# ISOBUS_Hardware_S3.net
KiCad netlist of a schematic drawn in EAGLE
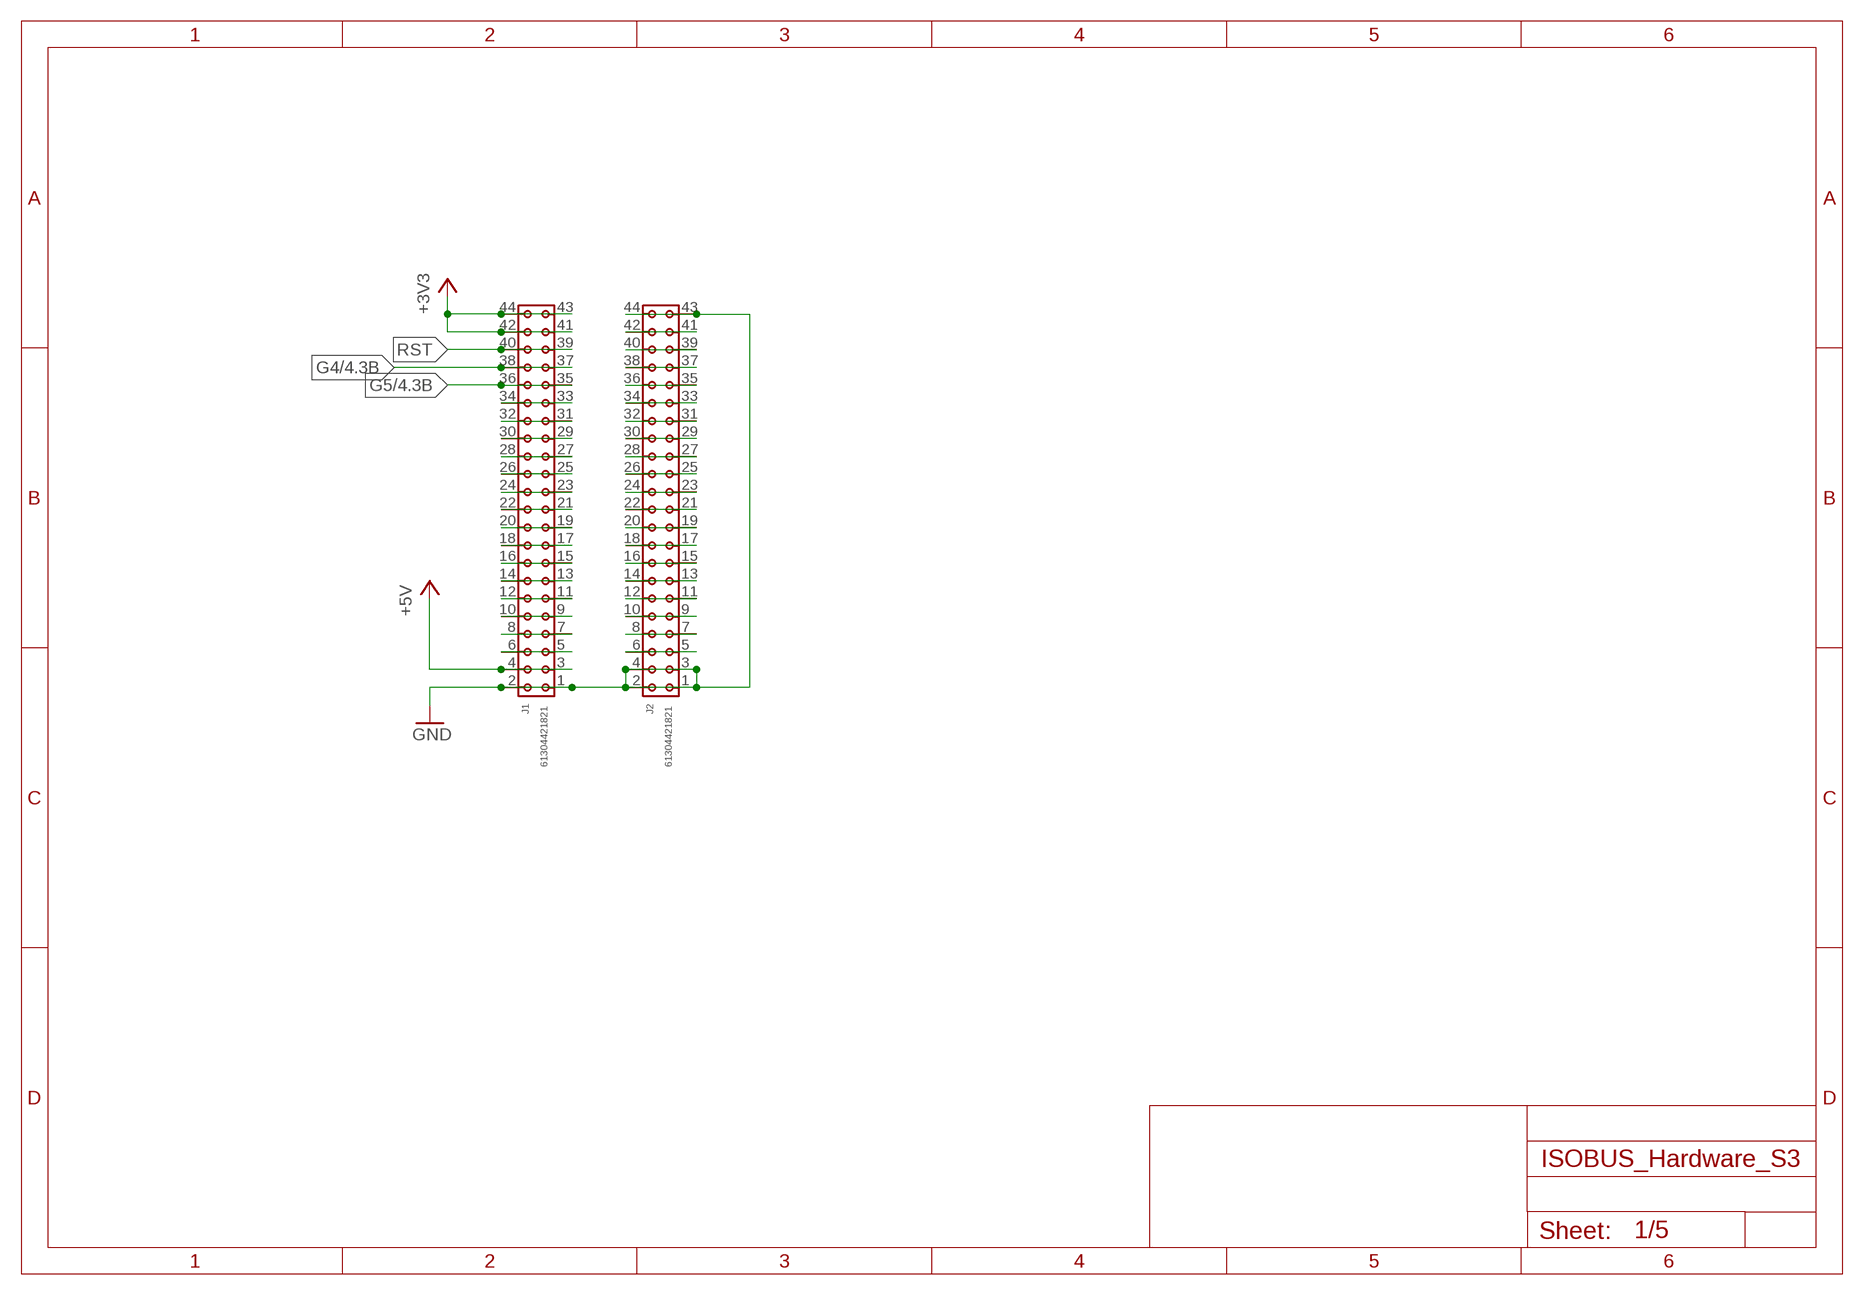
[diagram p0: schematic, sheet 1]
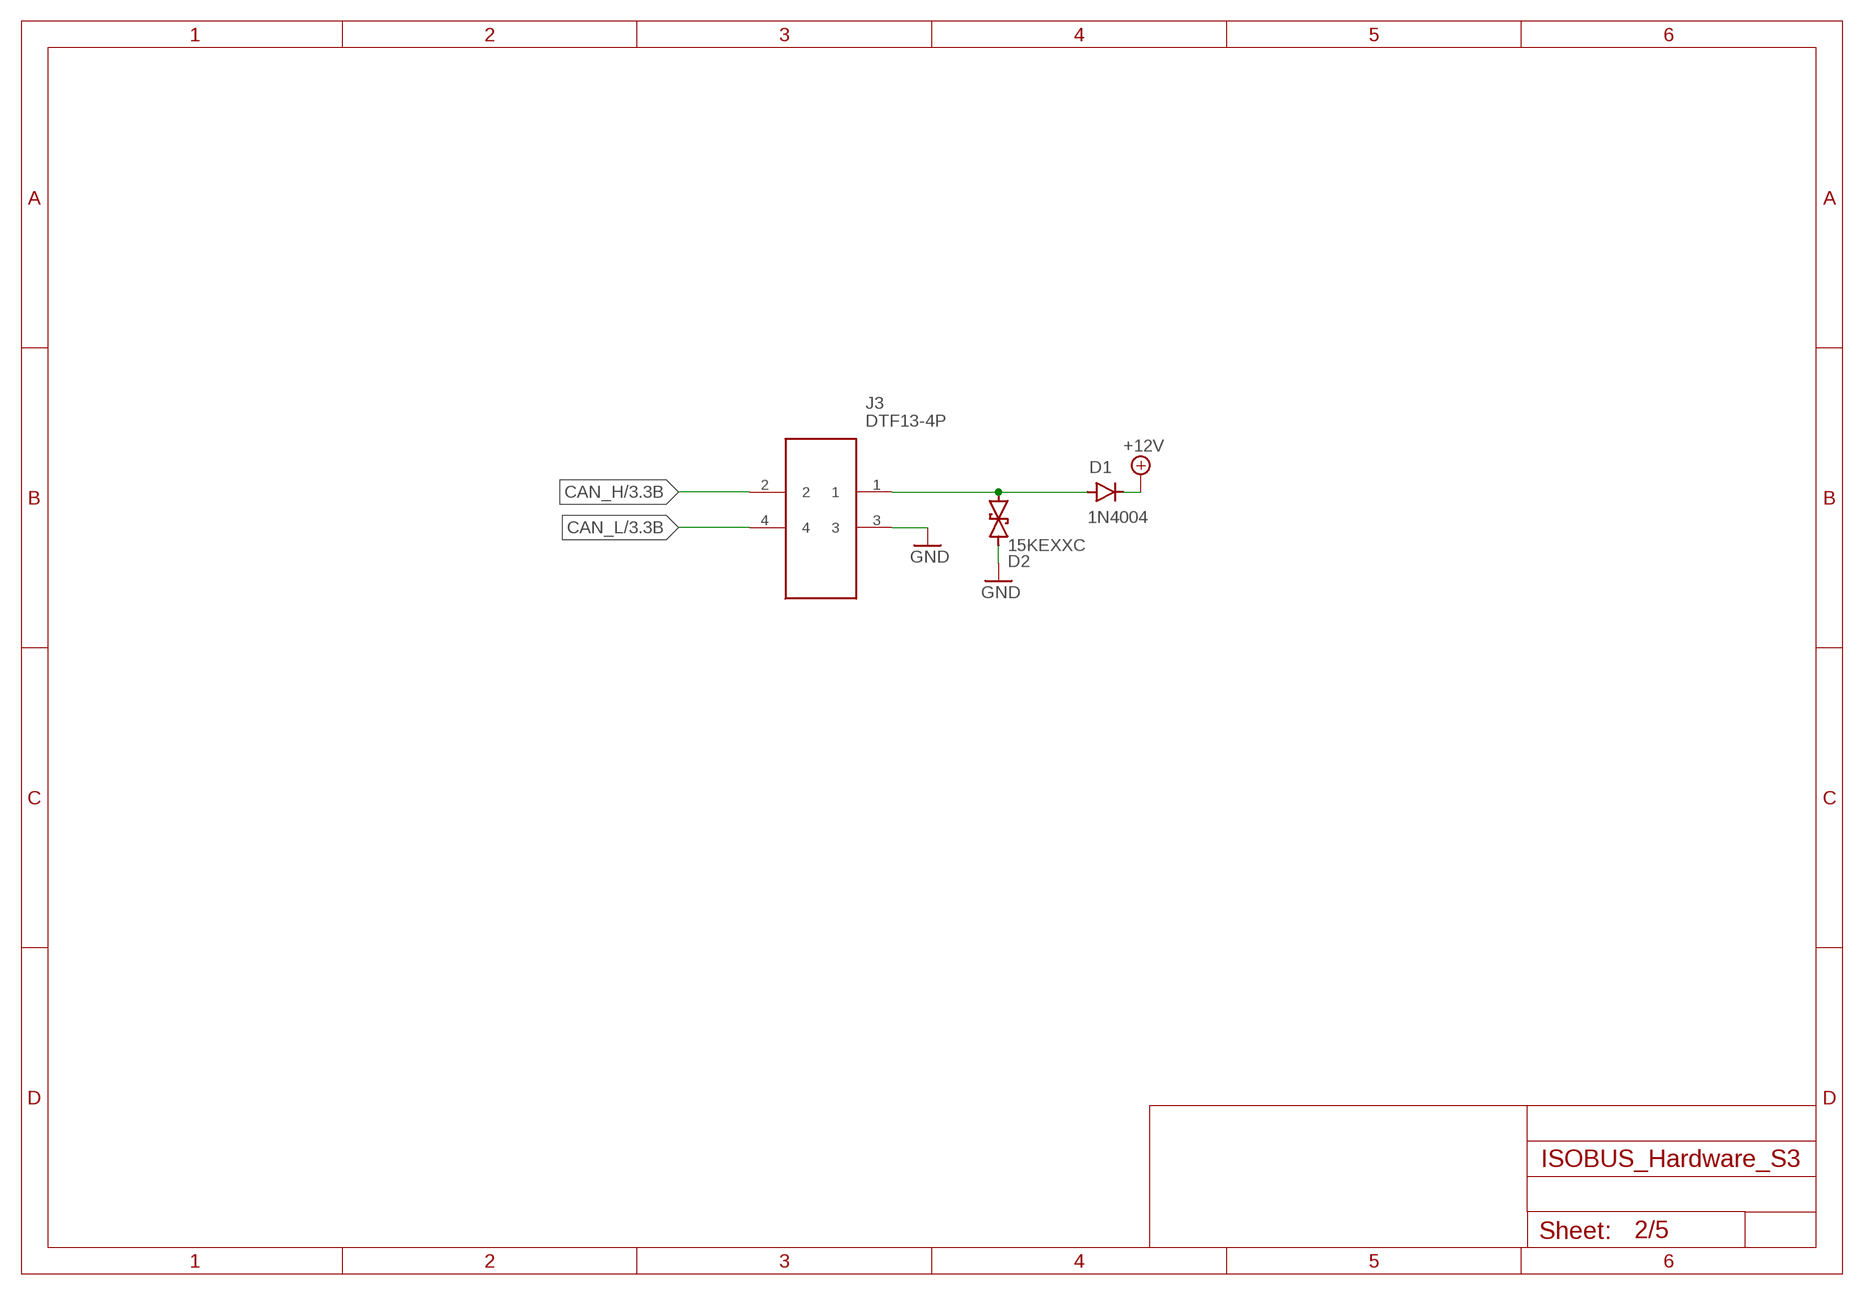
[diagram p1: schematic, sheet 2]
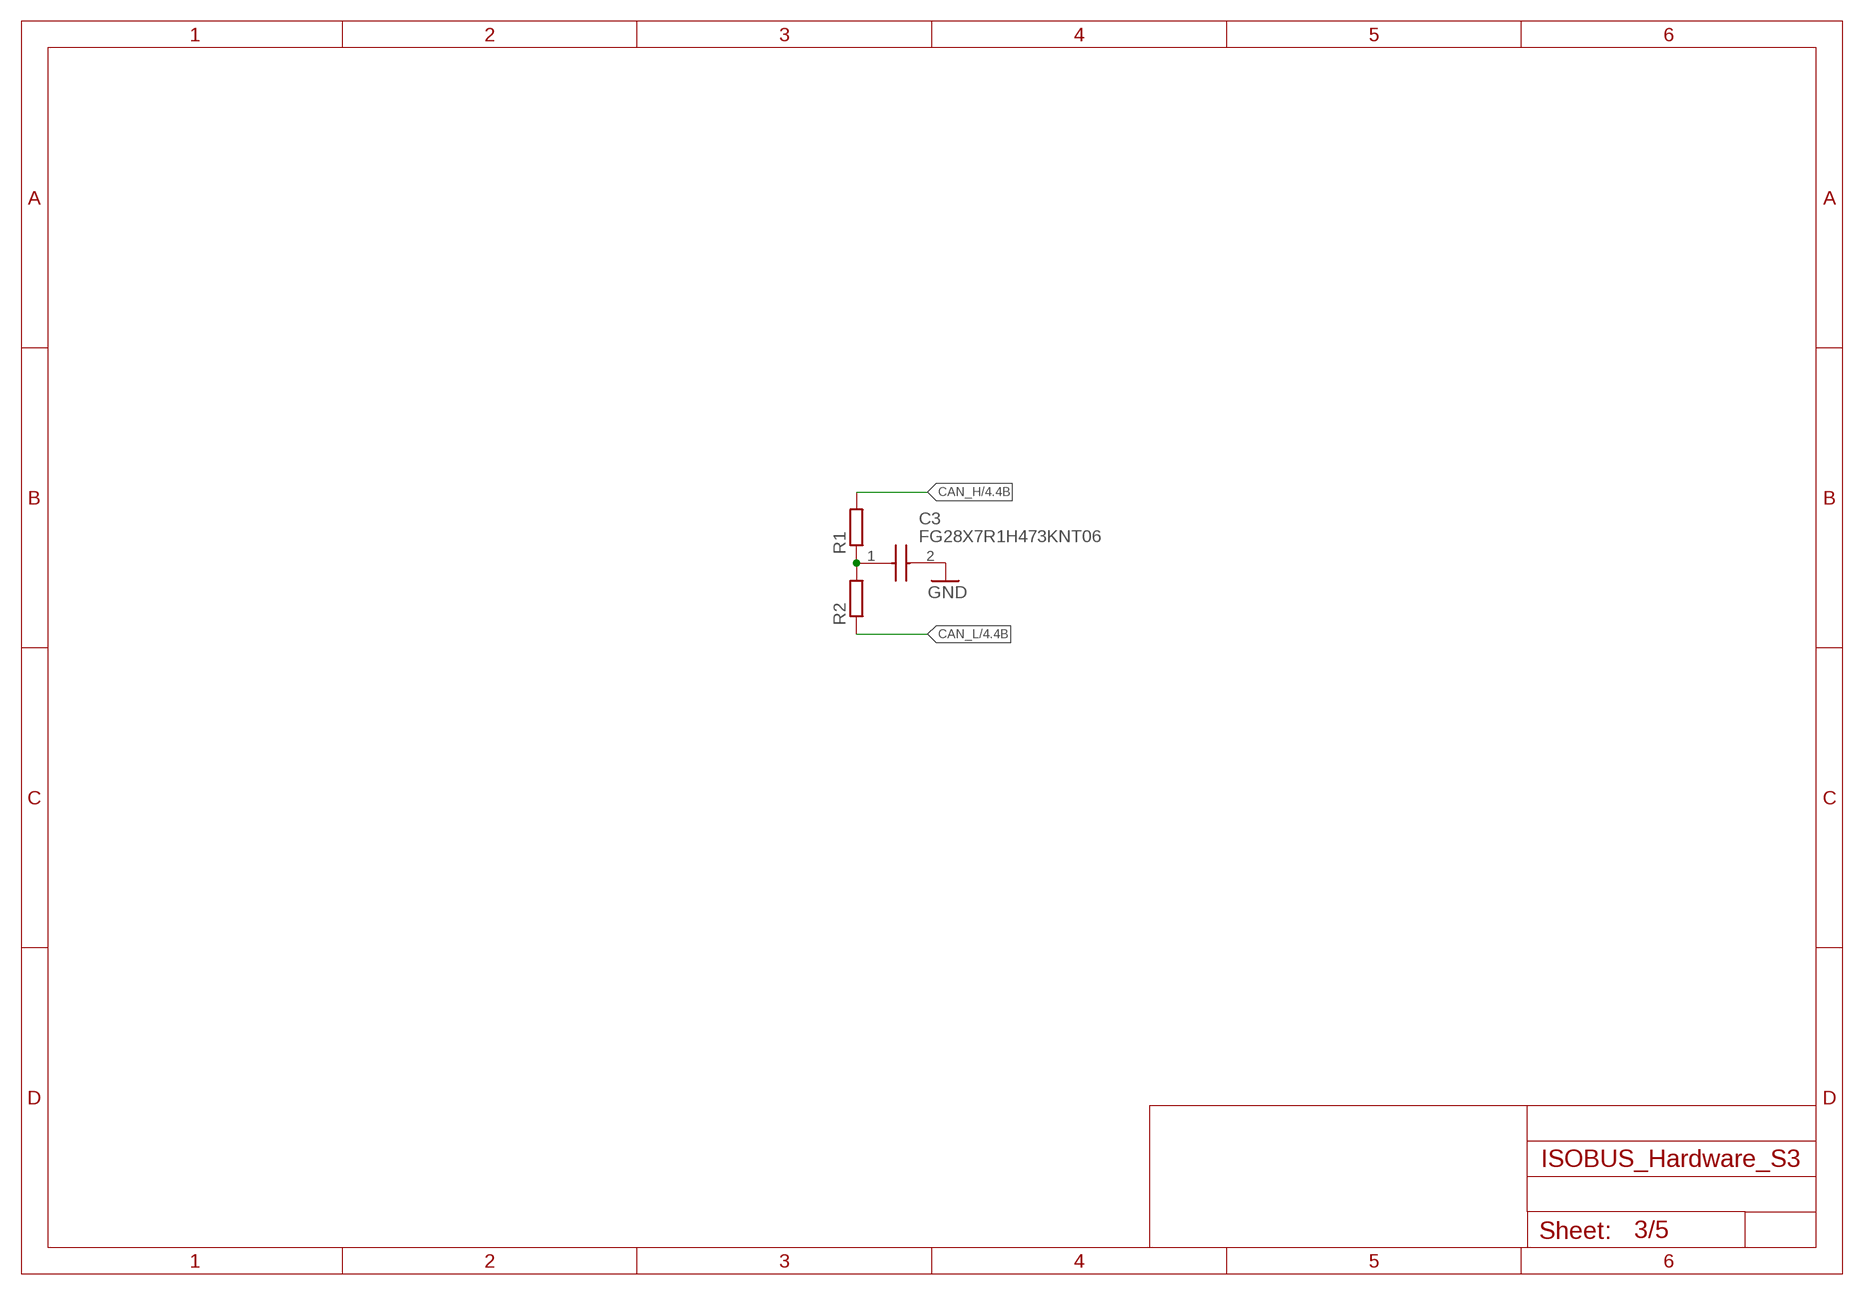
[diagram p2: schematic, sheet 3]
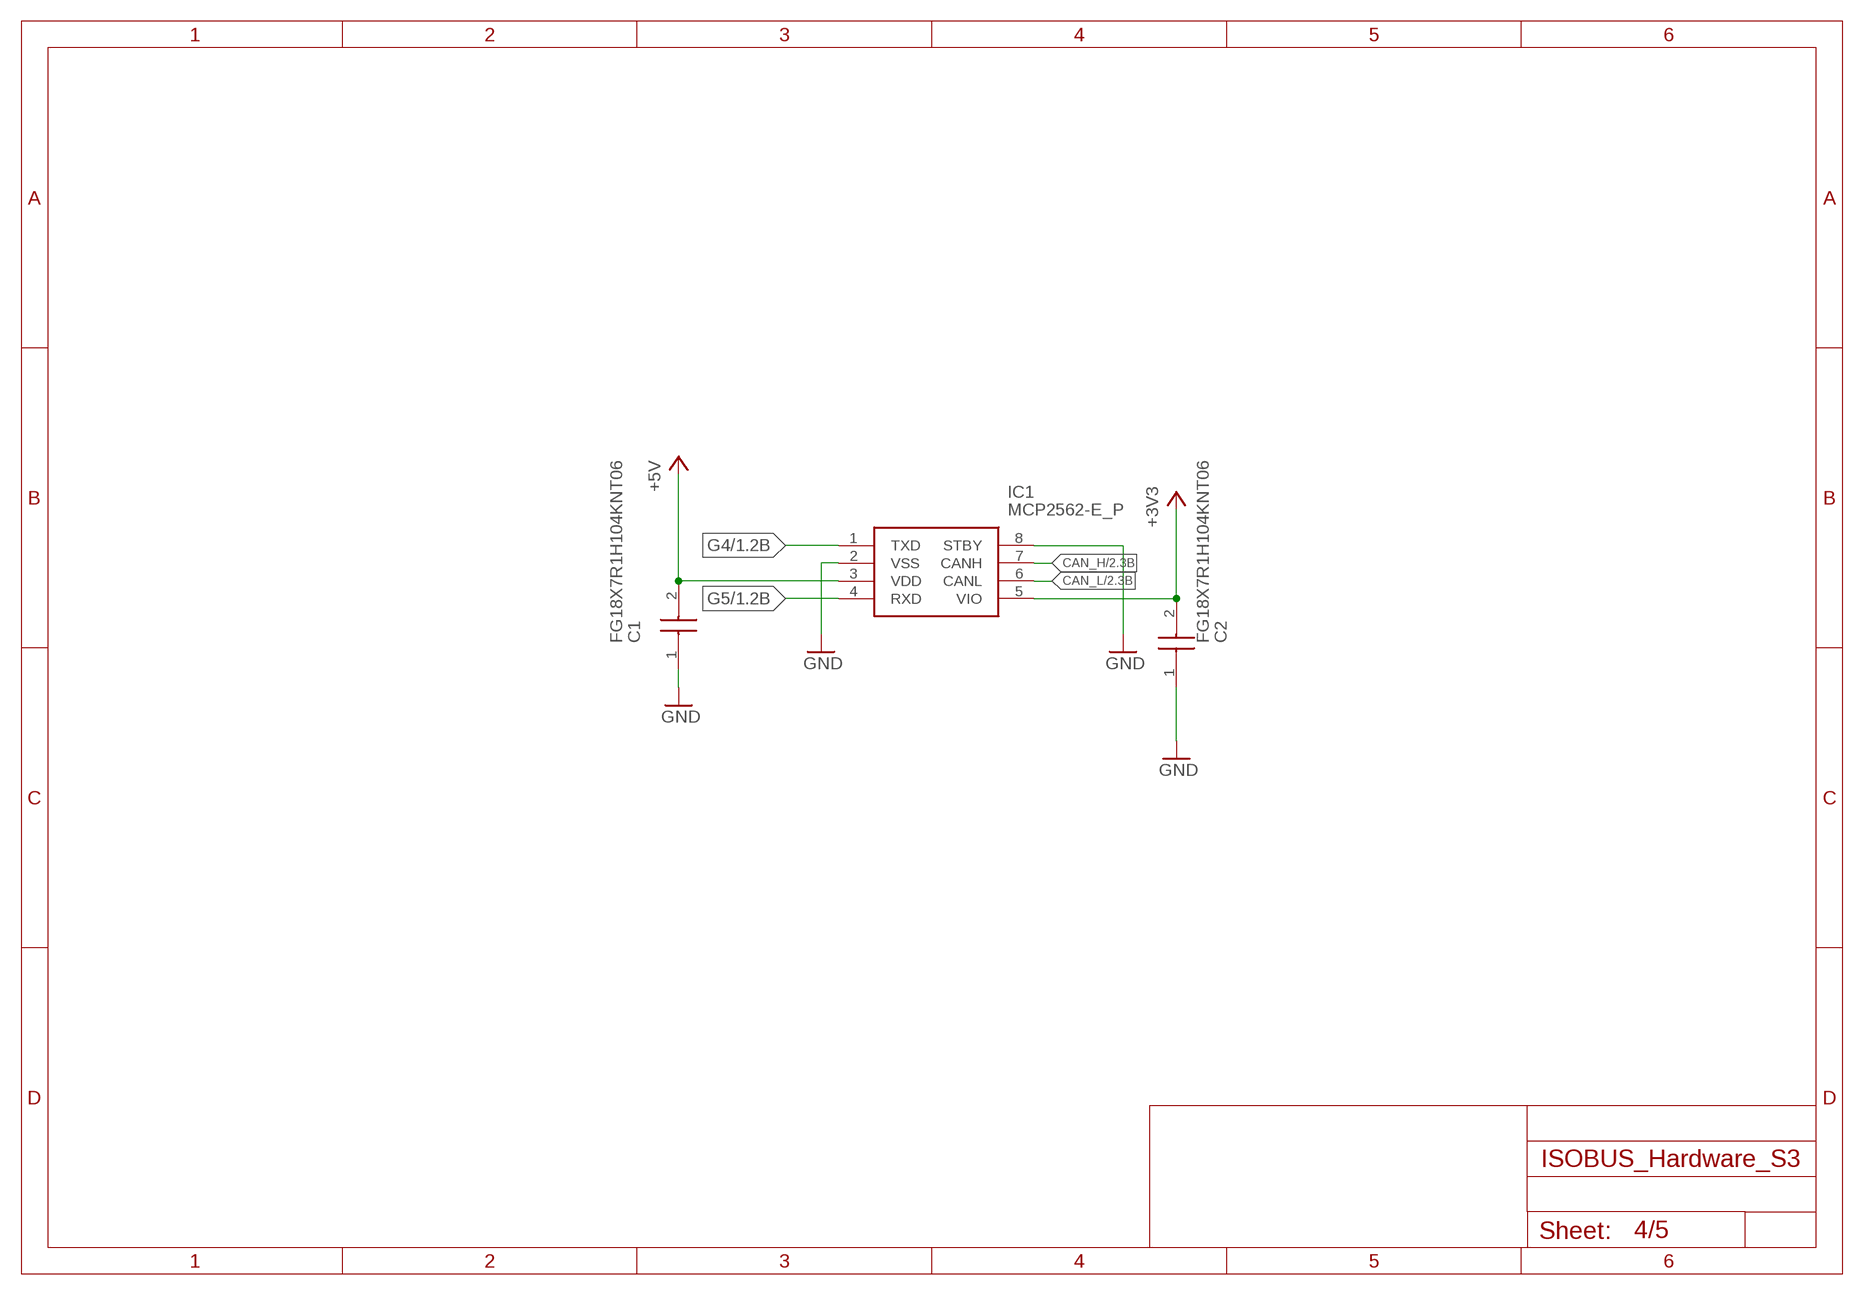
[diagram p3: schematic, sheet 4]
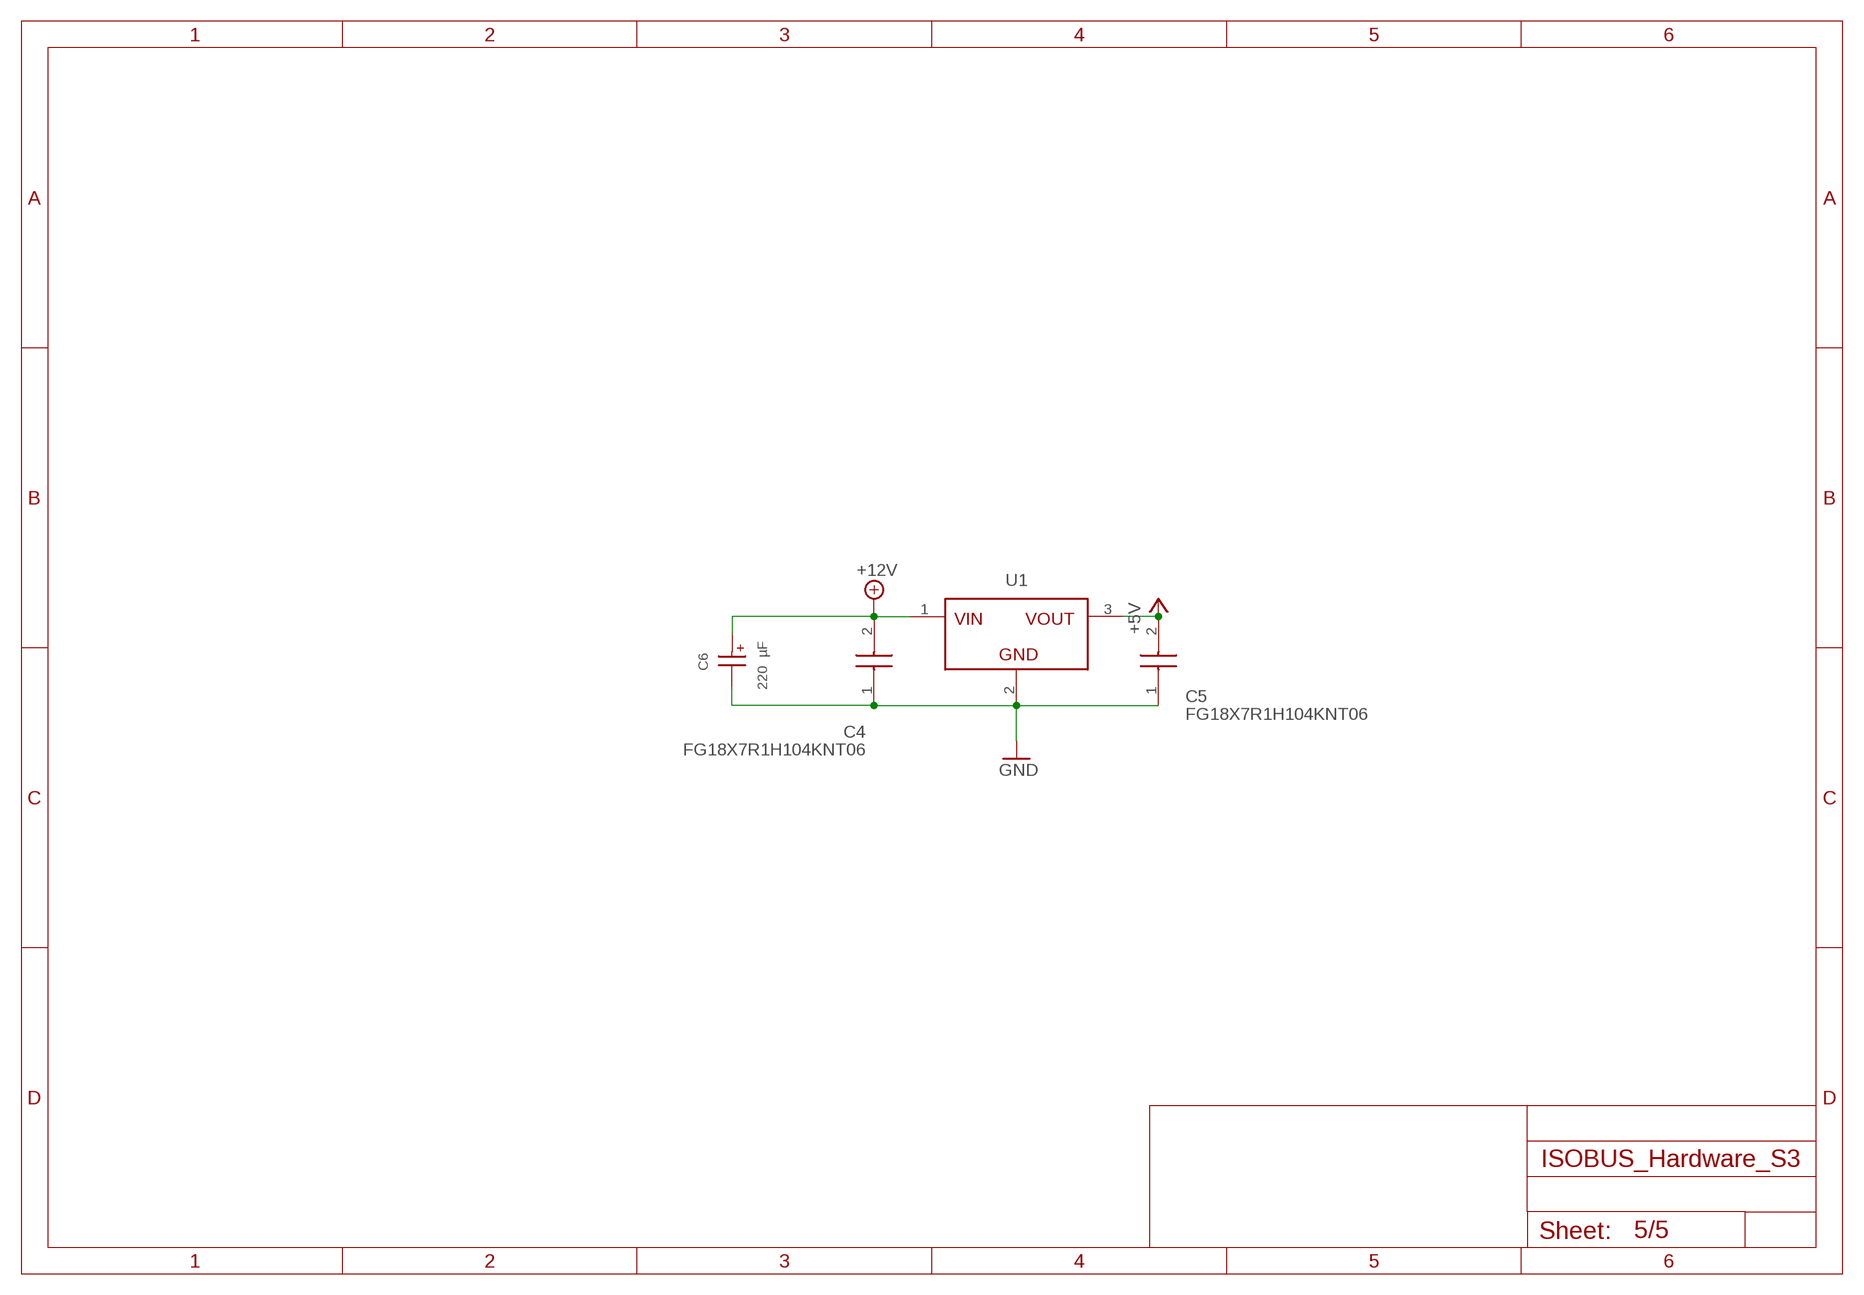
[diagram p4: schematic, sheet 5]

(export (version "E")
  (design (tool "Eeschema 10.0.6"))
  (components
    (comp (ref "C4")
      (value "FG18X7R1H104KNT06")
      (footprint "eagle-import:FG18C0G1H101JNT06")
      (fields (field (name "MOUSER_PART_NUMBER") "810-FG18X7R1H104KNT6"))
      (libsource (lib "eagle-import") (part "FG18X7R1H104KNT06"))
    )
    (comp (ref "C5")
      (value "FG18X7R1H104KNT06")
      (footprint "eagle-import:FG18C0G1H101JNT06")
      (fields (field (name "MOUSER_PART_NUMBER") "810-FG18X7R1H104KNT6"))
      (libsource (lib "eagle-import") (part "FG18X7R1H104KNT06"))
    )
    (comp (ref "C6")
      (value "220 µF")
      (footprint "eagle-import:WCAP-ATG8_6.3X11(DXL)")
      (libsource (lib "eagle-import") (part "WCAP-ATG8_6.3X11_860010373010"))
    )
    (comp (ref "U1")
      (value "MAGI³C-FDSM_SIP-3_173010542_173XXXX42")
      (footprint "eagle-import:MAGI³C-FDSM_173XXXX42")
      (libsource (lib "eagle-import") (part "MAGI³C-FDSM_SIP-3_173XXXX42_173010542"))
    )
    (comp (ref "J1")
      (value "61304421821")
      (footprint "eagle-import:61304421821")
      (libsource (lib "eagle-import") (part "6130XX21821_61304421821"))
    )
    (comp (ref "J2")
      (value "61304421821")
      (footprint "eagle-import:61304421821")
      (libsource (lib "eagle-import") (part "6130XX21821_61304421821"))
    )
    (comp (ref "C3")
      (value "FG28X7R1H473KNT06")
      (footprint "eagle-import:FG28")
      (fields (field (name "MOUSER_PART_NUMBER") "810-FG28X7R1H473KNT6"))
      (libsource (lib "eagle-import") (part "FG28X7R1H473KNT06"))
    )
    (comp (ref "R1")
      (value "R-EU_0204/7")
      (footprint "eagle-import:0204_7")
      (libsource (lib "eagle-import") (part "R-EU_0204/7"))
    )
    (comp (ref "R2")
      (value "R-EU_0204/7")
      (footprint "eagle-import:0204_7")
      (libsource (lib "eagle-import") (part "R-EU_0204/7"))
    )
    (comp (ref "D1")
      (value "1N4004")
      (footprint "eagle-import:DO-41")
      (fields
        (field (name "DIGIKEY_PART_NUMBER") "1N4004MSCT-ND")
        (field (name "MANUFACTURER") "Micro Commercial Co")
        (field (name "CREATED_BY") "PCBLayout.com")
      )
      (libsource (lib "eagle-import") (part "1N4004"))
    )
    (comp (ref "D2")
      (value "15KEXXC")
      (footprint "eagle-import:CB429-17")
      (libsource (lib "eagle-import") (part "15KEXXC"))
    )
    (comp (ref "J3")
      (value "DTF13-4P")
      (footprint "eagle-import:DTF134P")
      (fields (field (name "MOUSER_PART_NUMBER") "571-DTF13-4P"))
      (libsource (lib "eagle-import") (part "DTF13-4P"))
    )
    (comp (ref "C1")
      (value "FG18X7R1H104KNT06")
      (footprint "eagle-import:FG18C0G1H101JNT06")
      (fields (field (name "MOUSER_PART_NUMBER") "810-FG18X7R1H104KNT6"))
      (libsource (lib "eagle-import") (part "FG18X7R1H104KNT06"))
    )
    (comp (ref "C2")
      (value "FG18X7R1H104KNT06")
      (footprint "eagle-import:FG18C0G1H101JNT06")
      (fields (field (name "MOUSER_PART_NUMBER") "810-FG18X7R1H104KNT6"))
      (libsource (lib "eagle-import") (part "FG18X7R1H104KNT06"))
    )
    (comp (ref "IC1")
      (value "MCP2562-E_P")
      (footprint "eagle-import:DIP781W56P254L950H533Q8N")
      (fields
        (field (name "MANUFACTURER_PART_NUMBER") "MCP2562-E/P")
        (field (name "MOUSER_PART_NUMBER") "579-MCP2562-E/P")
      )
      (libsource (lib "eagle-import") (part "MCP2562-E_P"))
    )
  )
  (nets
    (net (code "1") (name "+3V3") (class "Default")
      (node (ref "C2") (pin "2") (pinfunction "2_2") (pintype "bidirectional"))
      (node (ref "IC1") (pin "5") (pinfunction "VIO_5") (pintype "bidirectional"))
      (node (ref "J1") (pin "41") (pinfunction "41_41") (pintype "passive"))
      (node (ref "J1") (pin "42") (pinfunction "42_42") (pintype "passive"))
      (node (ref "J1") (pin "43") (pinfunction "43_43") (pintype "passive"))
      (node (ref "J1") (pin "44") (pinfunction "44_44") (pintype "passive"))
    )
    (net (code "2") (name "+5V") (class "Default")
      (node (ref "C1") (pin "2") (pinfunction "2_2") (pintype "bidirectional"))
      (node (ref "C5") (pin "2") (pinfunction "2_2") (pintype "bidirectional"))
      (node (ref "IC1") (pin "3") (pinfunction "VDD_3") (pintype "bidirectional"))
      (node (ref "J1") (pin "3") (pinfunction "3_3") (pintype "passive"))
      (node (ref "J1") (pin "4") (pinfunction "4_4") (pintype "passive"))
      (node (ref "U1") (pin "3") (pinfunction "VOUT_3") (pintype "output"))
    )
    (net (code "3") (name "+12V") (class "Default")
      (node (ref "C4") (pin "2") (pinfunction "2_2") (pintype "bidirectional"))
      (node (ref "C6") (pin "1") (pinfunction "+_1") (pintype "passive"))
      (node (ref "D1") (pin "C") (pinfunction "C_C") (pintype "passive"))
      (node (ref "U1") (pin "1") (pinfunction "VIN_1") (pintype "input"))
    )
    (net (code "4") (name "CAN_H") (class "Default")
      (node (ref "IC1") (pin "7") (pinfunction "CANH_7") (pintype "bidirectional"))
      (node (ref "J3") (pin "2") (pinfunction "2_2") (pintype "bidirectional"))
      (node (ref "R1") (pin "2") (pinfunction "2_2") (pintype "passive"))
    )
    (net (code "5") (name "CAN_L") (class "Default")
      (node (ref "IC1") (pin "6") (pinfunction "CANL_6") (pintype "bidirectional"))
      (node (ref "J3") (pin "4") (pinfunction "4_4") (pintype "bidirectional"))
      (node (ref "R2") (pin "1") (pinfunction "1_1") (pintype "passive"))
    )
    (net (code "6") (name "G4") (class "Default")
      (node (ref "IC1") (pin "1") (pinfunction "TXD_1") (pintype "bidirectional"))
      (node (ref "J1") (pin "37") (pinfunction "37_37") (pintype "passive"))
      (node (ref "J1") (pin "38") (pinfunction "38_38") (pintype "passive"))
    )
    (net (code "7") (name "G5") (class "Default")
      (node (ref "IC1") (pin "4") (pinfunction "RXD_4") (pintype "bidirectional"))
      (node (ref "J1") (pin "35") (pinfunction "35_35") (pintype "passive"))
      (node (ref "J1") (pin "36") (pinfunction "36_36") (pintype "passive"))
    )
    (net (code "8") (name "GND") (class "Default")
      (node (ref "C1") (pin "1") (pinfunction "1_1") (pintype "bidirectional"))
      (node (ref "C2") (pin "1") (pinfunction "1_1") (pintype "bidirectional"))
      (node (ref "C3") (pin "2") (pinfunction "2_2") (pintype "bidirectional"))
      (node (ref "C4") (pin "1") (pinfunction "1_1") (pintype "bidirectional"))
      (node (ref "C5") (pin "1") (pinfunction "1_1") (pintype "bidirectional"))
      (node (ref "C6") (pin "2") (pinfunction "-_2") (pintype "passive"))
      (node (ref "D2") (pin "A") (pinfunction "1_A") (pintype "passive"))
      (node (ref "IC1") (pin "2") (pinfunction "VSS_2") (pintype "bidirectional"))
      (node (ref "IC1") (pin "8") (pinfunction "STBY_8") (pintype "bidirectional"))
      (node (ref "J1") (pin "1") (pinfunction "1_1") (pintype "passive"))
      (node (ref "J1") (pin "2") (pinfunction "2_2") (pintype "passive"))
      (node (ref "J2") (pin "1") (pinfunction "1_1") (pintype "passive"))
      (node (ref "J2") (pin "2") (pinfunction "2_2") (pintype "passive"))
      (node (ref "J2") (pin "3") (pinfunction "3_3") (pintype "passive"))
      (node (ref "J2") (pin "4") (pinfunction "4_4") (pintype "passive"))
      (node (ref "J2") (pin "43") (pinfunction "43_43") (pintype "passive"))
      (node (ref "J2") (pin "44") (pinfunction "44_44") (pintype "passive"))
      (node (ref "J3") (pin "3") (pinfunction "3_3") (pintype "bidirectional"))
      (node (ref "U1") (pin "2") (pinfunction "GND_2") (pintype "passive"))
    )
    (net (code "9") (name "Net-(C3-Pad1)") (class "Default")
      (node (ref "C3") (pin "1") (pinfunction "1_1") (pintype "bidirectional"))
      (node (ref "R1") (pin "1") (pinfunction "1_1") (pintype "passive"))
      (node (ref "R2") (pin "2") (pinfunction "2_2") (pintype "passive"))
    )
    (net (code "10") (name "Net-(D2-2)") (class "Default")
      (node (ref "D1") (pin "A") (pinfunction "A_A") (pintype "passive"))
      (node (ref "D2") (pin "C") (pinfunction "2_C") (pintype "passive"))
      (node (ref "J3") (pin "1") (pinfunction "1_1") (pintype "bidirectional"))
    )
    (net (code "11") (name "Net-(J1-Pad5)") (class "Default")
      (node (ref "J1") (pin "5") (pinfunction "5_5") (pintype "passive"))
      (node (ref "J1") (pin "6") (pinfunction "6_6") (pintype "passive"))
    )
    (net (code "12") (name "Net-(J1-Pad7)") (class "Default")
      (node (ref "J1") (pin "7") (pinfunction "7_7") (pintype "passive"))
      (node (ref "J1") (pin "8") (pinfunction "8_8") (pintype "passive"))
    )
    (net (code "13") (name "Net-(J1-Pad10)") (class "Default")
      (node (ref "J1") (pin "10") (pinfunction "10_10") (pintype "passive"))
      (node (ref "J1") (pin "9") (pinfunction "9_9") (pintype "passive"))
    )
    (net (code "14") (name "Net-(J1-Pad11)") (class "Default")
      (node (ref "J1") (pin "11") (pinfunction "11_11") (pintype "passive"))
      (node (ref "J1") (pin "12") (pinfunction "12_12") (pintype "passive"))
    )
    (net (code "15") (name "Net-(J1-Pad13)") (class "Default")
      (node (ref "J1") (pin "13") (pinfunction "13_13") (pintype "passive"))
      (node (ref "J1") (pin "14") (pinfunction "14_14") (pintype "passive"))
    )
    (net (code "16") (name "Net-(J1-Pad15)") (class "Default")
      (node (ref "J1") (pin "15") (pinfunction "15_15") (pintype "passive"))
      (node (ref "J1") (pin "16") (pinfunction "16_16") (pintype "passive"))
    )
    (net (code "17") (name "Net-(J1-Pad17)") (class "Default")
      (node (ref "J1") (pin "17") (pinfunction "17_17") (pintype "passive"))
      (node (ref "J1") (pin "18") (pinfunction "18_18") (pintype "passive"))
    )
    (net (code "18") (name "Net-(J1-Pad19)") (class "Default")
      (node (ref "J1") (pin "19") (pinfunction "19_19") (pintype "passive"))
      (node (ref "J1") (pin "20") (pinfunction "20_20") (pintype "passive"))
    )
    (net (code "19") (name "Net-(J1-Pad21)") (class "Default")
      (node (ref "J1") (pin "21") (pinfunction "21_21") (pintype "passive"))
      (node (ref "J1") (pin "22") (pinfunction "22_22") (pintype "passive"))
    )
    (net (code "20") (name "Net-(J1-Pad23)") (class "Default")
      (node (ref "J1") (pin "23") (pinfunction "23_23") (pintype "passive"))
      (node (ref "J1") (pin "24") (pinfunction "24_24") (pintype "passive"))
    )
    (net (code "21") (name "Net-(J1-Pad25)") (class "Default")
      (node (ref "J1") (pin "25") (pinfunction "25_25") (pintype "passive"))
      (node (ref "J1") (pin "26") (pinfunction "26_26") (pintype "passive"))
    )
    (net (code "22") (name "Net-(J1-Pad27)") (class "Default")
      (node (ref "J1") (pin "27") (pinfunction "27_27") (pintype "passive"))
      (node (ref "J1") (pin "28") (pinfunction "28_28") (pintype "passive"))
    )
    (net (code "23") (name "Net-(J1-Pad29)") (class "Default")
      (node (ref "J1") (pin "29") (pinfunction "29_29") (pintype "passive"))
      (node (ref "J1") (pin "30") (pinfunction "30_30") (pintype "passive"))
    )
    (net (code "24") (name "Net-(J1-Pad31)") (class "Default")
      (node (ref "J1") (pin "31") (pinfunction "31_31") (pintype "passive"))
      (node (ref "J1") (pin "32") (pinfunction "32_32") (pintype "passive"))
    )
    (net (code "25") (name "Net-(J1-Pad33)") (class "Default")
      (node (ref "J1") (pin "33") (pinfunction "33_33") (pintype "passive"))
      (node (ref "J1") (pin "34") (pinfunction "34_34") (pintype "passive"))
    )
    (net (code "26") (name "Net-(J2-Pad5)") (class "Default")
      (node (ref "J2") (pin "5") (pinfunction "5_5") (pintype "passive"))
      (node (ref "J2") (pin "6") (pinfunction "6_6") (pintype "passive"))
    )
    (net (code "27") (name "Net-(J2-Pad7)") (class "Default")
      (node (ref "J2") (pin "7") (pinfunction "7_7") (pintype "passive"))
      (node (ref "J2") (pin "8") (pinfunction "8_8") (pintype "passive"))
    )
    (net (code "28") (name "Net-(J2-Pad10)") (class "Default")
      (node (ref "J2") (pin "10") (pinfunction "10_10") (pintype "passive"))
      (node (ref "J2") (pin "9") (pinfunction "9_9") (pintype "passive"))
    )
    (net (code "29") (name "Net-(J2-Pad11)") (class "Default")
      (node (ref "J2") (pin "11") (pinfunction "11_11") (pintype "passive"))
      (node (ref "J2") (pin "12") (pinfunction "12_12") (pintype "passive"))
    )
    (net (code "30") (name "Net-(J2-Pad13)") (class "Default")
      (node (ref "J2") (pin "13") (pinfunction "13_13") (pintype "passive"))
      (node (ref "J2") (pin "14") (pinfunction "14_14") (pintype "passive"))
    )
    (net (code "31") (name "Net-(J2-Pad15)") (class "Default")
      (node (ref "J2") (pin "15") (pinfunction "15_15") (pintype "passive"))
      (node (ref "J2") (pin "16") (pinfunction "16_16") (pintype "passive"))
    )
    (net (code "32") (name "Net-(J2-Pad17)") (class "Default")
      (node (ref "J2") (pin "17") (pinfunction "17_17") (pintype "passive"))
      (node (ref "J2") (pin "18") (pinfunction "18_18") (pintype "passive"))
    )
    (net (code "33") (name "Net-(J2-Pad19)") (class "Default")
      (node (ref "J2") (pin "19") (pinfunction "19_19") (pintype "passive"))
      (node (ref "J2") (pin "20") (pinfunction "20_20") (pintype "passive"))
    )
    (net (code "34") (name "Net-(J2-Pad21)") (class "Default")
      (node (ref "J2") (pin "21") (pinfunction "21_21") (pintype "passive"))
      (node (ref "J2") (pin "22") (pinfunction "22_22") (pintype "passive"))
    )
    (net (code "35") (name "Net-(J2-Pad23)") (class "Default")
      (node (ref "J2") (pin "23") (pinfunction "23_23") (pintype "passive"))
      (node (ref "J2") (pin "24") (pinfunction "24_24") (pintype "passive"))
    )
    (net (code "36") (name "Net-(J2-Pad25)") (class "Default")
      (node (ref "J2") (pin "25") (pinfunction "25_25") (pintype "passive"))
      (node (ref "J2") (pin "26") (pinfunction "26_26") (pintype "passive"))
    )
    (net (code "37") (name "Net-(J2-Pad27)") (class "Default")
      (node (ref "J2") (pin "27") (pinfunction "27_27") (pintype "passive"))
      (node (ref "J2") (pin "28") (pinfunction "28_28") (pintype "passive"))
    )
    (net (code "38") (name "Net-(J2-Pad29)") (class "Default")
      (node (ref "J2") (pin "29") (pinfunction "29_29") (pintype "passive"))
      (node (ref "J2") (pin "30") (pinfunction "30_30") (pintype "passive"))
    )
    (net (code "39") (name "Net-(J2-Pad31)") (class "Default")
      (node (ref "J2") (pin "31") (pinfunction "31_31") (pintype "passive"))
      (node (ref "J2") (pin "32") (pinfunction "32_32") (pintype "passive"))
    )
    (net (code "40") (name "Net-(J2-Pad33)") (class "Default")
      (node (ref "J2") (pin "33") (pinfunction "33_33") (pintype "passive"))
      (node (ref "J2") (pin "34") (pinfunction "34_34") (pintype "passive"))
    )
    (net (code "41") (name "Net-(J2-Pad35)") (class "Default")
      (node (ref "J2") (pin "35") (pinfunction "35_35") (pintype "passive"))
      (node (ref "J2") (pin "36") (pinfunction "36_36") (pintype "passive"))
    )
    (net (code "42") (name "Net-(J2-Pad37)") (class "Default")
      (node (ref "J2") (pin "37") (pinfunction "37_37") (pintype "passive"))
      (node (ref "J2") (pin "38") (pinfunction "38_38") (pintype "passive"))
    )
    (net (code "43") (name "Net-(J2-Pad39)") (class "Default")
      (node (ref "J2") (pin "39") (pinfunction "39_39") (pintype "passive"))
      (node (ref "J2") (pin "40") (pinfunction "40_40") (pintype "passive"))
    )
    (net (code "44") (name "Net-(J2-Pad41)") (class "Default")
      (node (ref "J2") (pin "41") (pinfunction "41_41") (pintype "passive"))
      (node (ref "J2") (pin "42") (pinfunction "42_42") (pintype "passive"))
    )
    (net (code "45") (name "RST") (class "Default")
      (node (ref "J1") (pin "39") (pinfunction "39_39") (pintype "passive"))
      (node (ref "J1") (pin "40") (pinfunction "40_40") (pintype "passive"))
    )
  )
)
